# Binary_Blaster.net
KiCad netlist of a schematic drawn in EAGLE
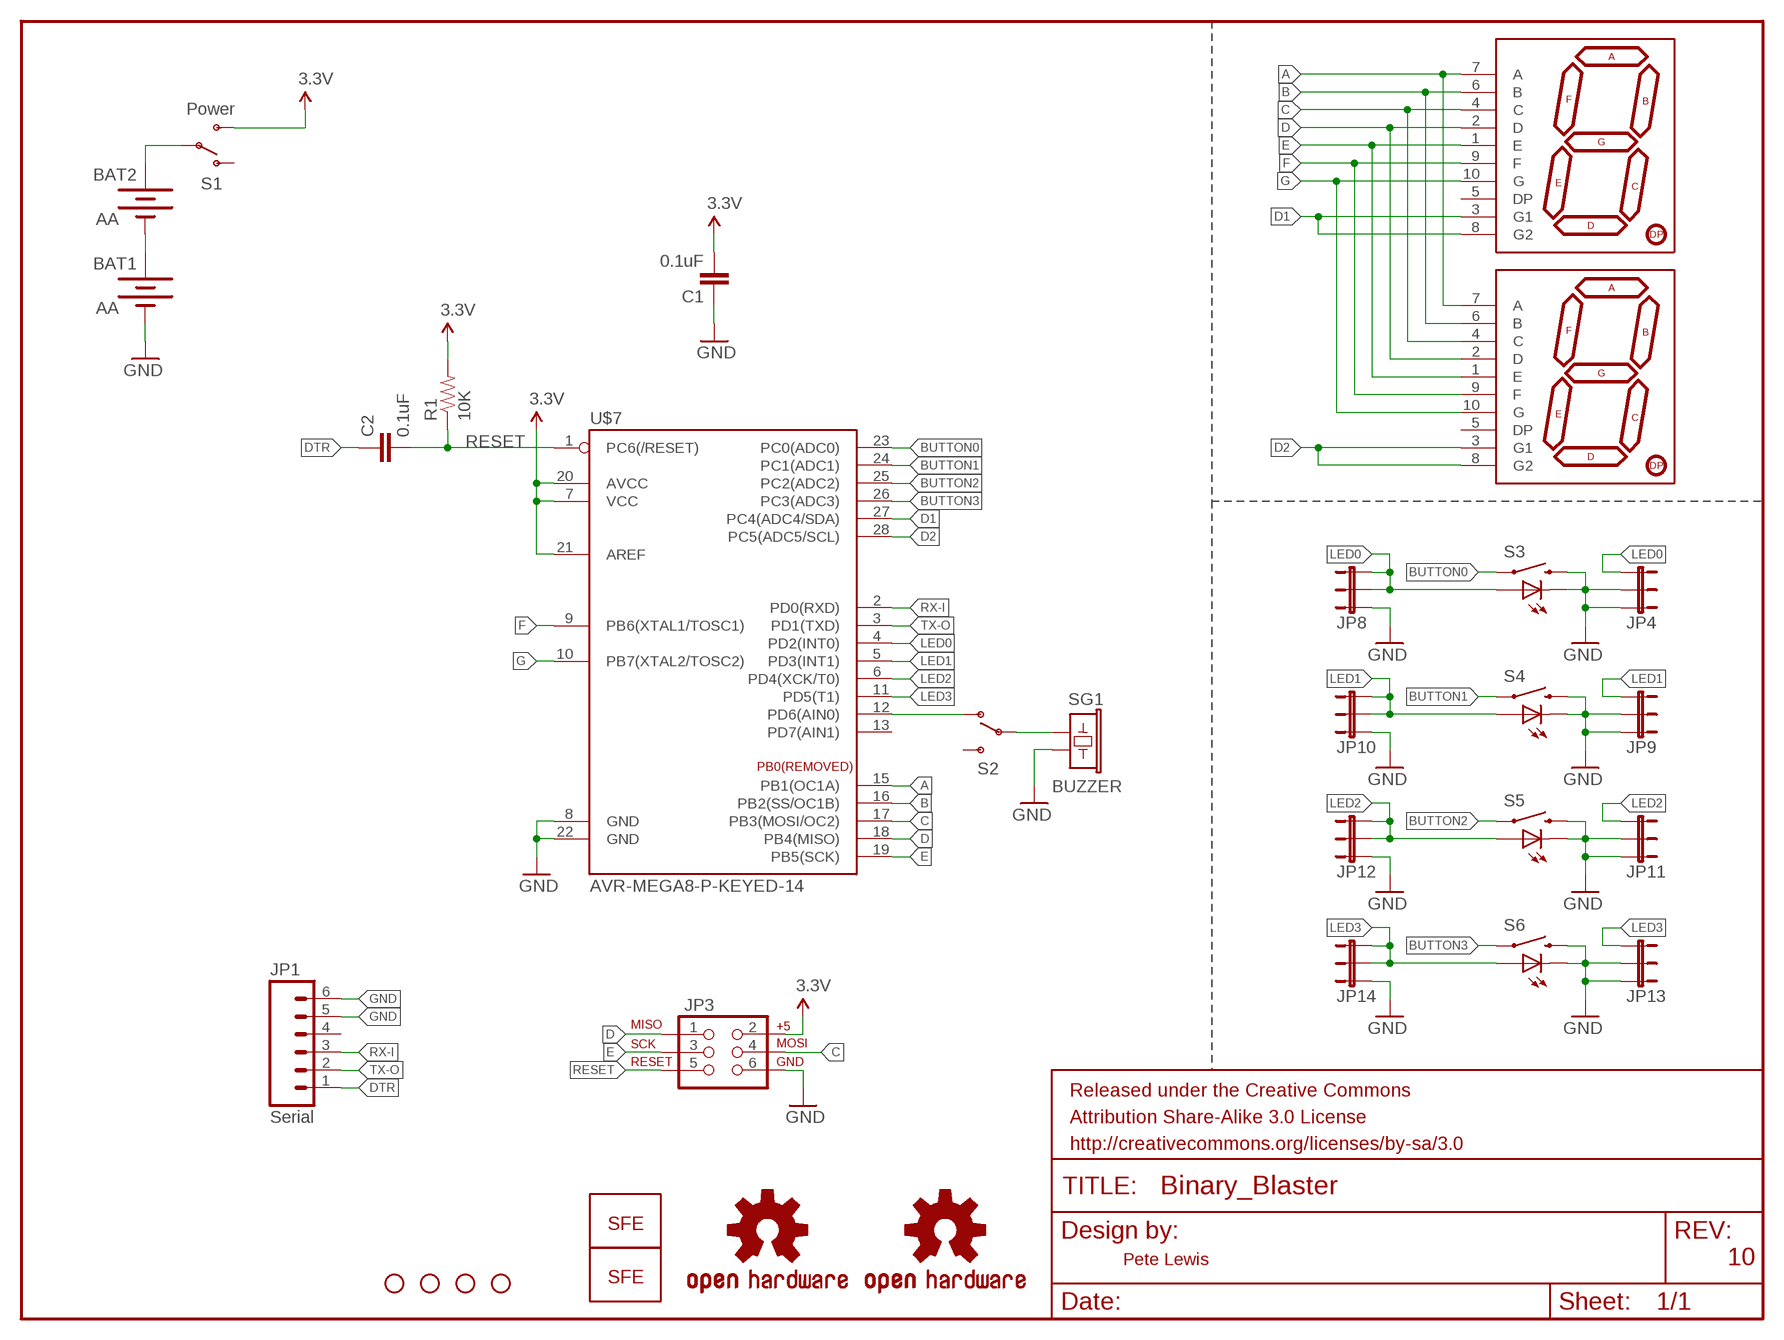
[diagram p0: schematic, sheet 1]

(export (version "E")
  (design (tool "Eeschema 10.0.6"))
  (components
    (comp (ref "BAT1")
      (value "AA")
      (footprint "eagle-import:BATTERY-AA-KIT")
      (libsource (lib "eagle-import") (part "BATTERYAA-KIT"))
    )
    (comp (ref "BAT2")
      (value "AA")
      (footprint "eagle-import:BATTERY-AA-KIT")
      (libsource (lib "eagle-import") (part "BATTERYAA-KIT"))
    )
    (comp (ref "C1")
      (value "0.1uF")
      (footprint "eagle-import:CAP-PTH-SMALL-KIT")
      (libsource (lib "eagle-import") (part "0.1UF-50V-20%(PTH)KIT-EZ"))
    )
    (comp (ref "C2")
      (value "0.1uF")
      (footprint "eagle-import:CAP-PTH-SMALL-KIT")
      (libsource (lib "eagle-import") (part "0.1UF-50V-20%(PTH)KIT-EZ"))
    )
    (comp (ref "FRAME1")
      (value "FRAME-LETTER")
      (footprint "eagle-import:CREATIVE_COMMONS")
      (libsource (lib "eagle-import") (part "FRAME-LETTER"))
    )
    (comp (ref "JP1")
      (value "Serial")
      (footprint "eagle-import:1X06-NOSILK")
      (libsource (lib "eagle-import") (part "M06-SFENOSILK"))
    )
    (comp (ref "JP2")
      (value "STAND-OFF")
      (footprint "eagle-import:STAND-OFF")
      (libsource (lib "eagle-import") (part "STAND-OFF"))
    )
    (comp (ref "JP3")
      (value "AVR_SPI_PRG_6NS")
      (footprint "eagle-import:2X3-NS")
      (libsource (lib "eagle-import") (part "AVR_SPI_PRG_6NS"))
    )
    (comp (ref "JP4")
      (value "JUMPER-3SMD")
      (footprint "eagle-import:SJ_3")
      (libsource (lib "eagle-import") (part "JUMPER-3SMD"))
    )
    (comp (ref "JP5")
      (value "STAND-OFF")
      (footprint "eagle-import:STAND-OFF")
      (libsource (lib "eagle-import") (part "STAND-OFF"))
    )
    (comp (ref "JP6")
      (value "STAND-OFF")
      (footprint "eagle-import:STAND-OFF")
      (libsource (lib "eagle-import") (part "STAND-OFF"))
    )
    (comp (ref "JP7")
      (value "STAND-OFF")
      (footprint "eagle-import:STAND-OFF")
      (libsource (lib "eagle-import") (part "STAND-OFF"))
    )
    (comp (ref "JP8")
      (value "JUMPER-3SMD")
      (footprint "eagle-import:SJ_3")
      (libsource (lib "eagle-import") (part "JUMPER-3SMD"))
    )
    (comp (ref "JP9")
      (value "JUMPER-3SMD")
      (footprint "eagle-import:SJ_3")
      (libsource (lib "eagle-import") (part "JUMPER-3SMD"))
    )
    (comp (ref "JP10")
      (value "JUMPER-3SMD")
      (footprint "eagle-import:SJ_3")
      (libsource (lib "eagle-import") (part "JUMPER-3SMD"))
    )
    (comp (ref "JP11")
      (value "JUMPER-3SMD")
      (footprint "eagle-import:SJ_3")
      (libsource (lib "eagle-import") (part "JUMPER-3SMD"))
    )
    (comp (ref "JP12")
      (value "JUMPER-3SMD")
      (footprint "eagle-import:SJ_3")
      (libsource (lib "eagle-import") (part "JUMPER-3SMD"))
    )
    (comp (ref "JP13")
      (value "JUMPER-3SMD")
      (footprint "eagle-import:SJ_3")
      (libsource (lib "eagle-import") (part "JUMPER-3SMD"))
    )
    (comp (ref "JP14")
      (value "JUMPER-3SMD")
      (footprint "eagle-import:SJ_3")
      (libsource (lib "eagle-import") (part "JUMPER-3SMD"))
    )
    (comp (ref "LOGO1")
      (value "LOGO-SFENEW")
      (footprint "eagle-import:SFE-NEW-WEBLOGO")
      (libsource (lib "eagle-import") (part "LOGO-SFENEW"))
    )
    (comp (ref "LOGO2")
      (value "LOGO-SFENEW")
      (footprint "eagle-import:SFE-NEW-WEBLOGO")
      (libsource (lib "eagle-import") (part "LOGO-SFENEW"))
    )
    (comp (ref "R1")
      (value "10K")
      (footprint "eagle-import:AXIAL-0.3-KIT")
      (libsource (lib "eagle-import") (part "10KOHM1/6W5%(PTH)KIT"))
    )
    (comp (ref "S1")
      (value "Power")
      (footprint "eagle-import:SWITCH-SPDT_KIT")
      (libsource (lib "eagle-import") (part "SWITCH-SPDTKIT"))
    )
    (comp (ref "S2")
      (value "SWITCH-SPDTKIT")
      (footprint "eagle-import:SWITCH-SPDT_KIT")
      (libsource (lib "eagle-import") (part "SWITCH-SPDTKIT"))
    )
    (comp (ref "S3")
      (value "SWITCH-MOMENTARY-LEDEZ")
      (footprint "eagle-import:TACTILE-PTH-LED-12MM-EZ")
      (libsource (lib "eagle-import") (part "SWITCH-MOMENTARY-LEDEZ"))
    )
    (comp (ref "S4")
      (value "SWITCH-MOMENTARY-LEDEZ")
      (footprint "eagle-import:TACTILE-PTH-LED-12MM-EZ")
      (libsource (lib "eagle-import") (part "SWITCH-MOMENTARY-LEDEZ"))
    )
    (comp (ref "S5")
      (value "SWITCH-MOMENTARY-LEDEZ")
      (footprint "eagle-import:TACTILE-PTH-LED-12MM-EZ")
      (libsource (lib "eagle-import") (part "SWITCH-MOMENTARY-LEDEZ"))
    )
    (comp (ref "S6")
      (value "SWITCH-MOMENTARY-LEDEZ")
      (footprint "eagle-import:TACTILE-PTH-LED-12MM-EZ")
      (libsource (lib "eagle-import") (part "SWITCH-MOMENTARY-LEDEZ"))
    )
    (comp (ref "SG1")
      (value "BUZZER")
      (footprint "eagle-import:BUZZER-12MM-KIT")
      (libsource (lib "eagle-import") (part "BUZZERPTH-KIT"))
    )
    (comp (ref "U$1")
      (value "7-SEGMENT-DISPLAY-1\"-REDEZ")
      (footprint "eagle-import:7-SEGMENT-1_PTH-EZ")
      (libsource (lib "eagle-import") (part "7-SEGMENT-DISPLAY-1{dblquote}-REDEZ"))
    )
    (comp (ref "U$2")
      (value "OSHW-LOGOL")
      (footprint "eagle-import:OSHW-LOGO-L")
      (libsource (lib "eagle-import") (part "OSHW-LOGOL"))
    )
    (comp (ref "U$3")
      (value "OSHW-LOGOS")
      (footprint "eagle-import:OSHW-LOGO-S")
      (libsource (lib "eagle-import") (part "OSHW-LOGOS"))
    )
    (comp (ref "U$6")
      (value "7-SEGMENT-DISPLAY-1\"-REDEZ")
      (footprint "eagle-import:7-SEGMENT-1_PTH-EZ")
      (libsource (lib "eagle-import") (part "7-SEGMENT-DISPLAY-1{dblquote}-REDEZ"))
    )
    (comp (ref "U$7")
      (value "AVR-MEGA8-P-KEYED-14")
      (footprint "eagle-import:DIL28-3_KEYED-14")
      (libsource (lib "eagle-import") (part "AVR-MEGA8-P-KEYED-14"))
    )
  )
  (nets
    (net (code "1") (name "3.3V") (class "Default")
      (node (ref "C1") (pin "2") (pinfunction "2_2") (pintype "passive"))
      (node (ref "JP3") (pin "2") (pinfunction "2_2") (pintype "passive"))
      (node (ref "R1") (pin "P$2") (pinfunction "2_P$2") (pintype "passive"))
      (node (ref "S1") (pin "3") (pinfunction "S_3") (pintype "passive"))
      (node (ref "U$7") (pin "20") (pinfunction "AVCC_20") (pintype "bidirectional"))
      (node (ref "U$7") (pin "21") (pinfunction "AREF_21") (pintype "bidirectional"))
      (node (ref "U$7") (pin "7") (pinfunction "VCC_7") (pintype "bidirectional"))
    )
    (net (code "2") (name "A") (class "Default")
      (node (ref "U$1") (pin "7") (pinfunction "A_7") (pintype "bidirectional"))
      (node (ref "U$6") (pin "7") (pinfunction "A_7") (pintype "bidirectional"))
      (node (ref "U$7") (pin "15") (pinfunction "PB1(OC1A)_15") (pintype "bidirectional"))
    )
    (net (code "3") (name "B") (class "Default")
      (node (ref "U$1") (pin "6") (pinfunction "B_6") (pintype "bidirectional"))
      (node (ref "U$6") (pin "6") (pinfunction "B_6") (pintype "bidirectional"))
      (node (ref "U$7") (pin "16") (pinfunction "PB2(SS/OC1B)_16") (pintype "bidirectional"))
    )
    (net (code "4") (name "BUTTON0") (class "Default")
      (node (ref "S3") (pin "4") (pinfunction "1_4") (pintype "passive"))
      (node (ref "U$7") (pin "23") (pinfunction "PC0(ADC0)_23") (pintype "bidirectional"))
    )
    (net (code "5") (name "BUTTON1") (class "Default")
      (node (ref "S4") (pin "4") (pinfunction "1_4") (pintype "passive"))
      (node (ref "U$7") (pin "24") (pinfunction "PC1(ADC1)_24") (pintype "bidirectional"))
    )
    (net (code "6") (name "BUTTON2") (class "Default")
      (node (ref "S5") (pin "4") (pinfunction "1_4") (pintype "passive"))
      (node (ref "U$7") (pin "25") (pinfunction "PC2(ADC2)_25") (pintype "bidirectional"))
    )
    (net (code "7") (name "BUTTON3") (class "Default")
      (node (ref "S6") (pin "4") (pinfunction "1_4") (pintype "passive"))
      (node (ref "U$7") (pin "26") (pinfunction "PC3(ADC3)_26") (pintype "bidirectional"))
    )
    (net (code "8") (name "C") (class "Default")
      (node (ref "JP3") (pin "4") (pinfunction "4_4") (pintype "passive"))
      (node (ref "U$1") (pin "4") (pinfunction "C_4") (pintype "bidirectional"))
      (node (ref "U$6") (pin "4") (pinfunction "C_4") (pintype "bidirectional"))
      (node (ref "U$7") (pin "17") (pinfunction "PB3(MOSI/OC2)_17") (pintype "bidirectional"))
    )
    (net (code "9") (name "D") (class "Default")
      (node (ref "JP3") (pin "1") (pinfunction "1_1") (pintype "passive"))
      (node (ref "U$1") (pin "2") (pinfunction "D_2") (pintype "bidirectional"))
      (node (ref "U$6") (pin "2") (pinfunction "D_2") (pintype "bidirectional"))
      (node (ref "U$7") (pin "18") (pinfunction "PB4(MISO)_18") (pintype "bidirectional"))
    )
    (net (code "10") (name "D1") (class "Default")
      (node (ref "U$1") (pin "3") (pinfunction "G1_3") (pintype "bidirectional"))
      (node (ref "U$1") (pin "8") (pinfunction "G2_8") (pintype "bidirectional"))
      (node (ref "U$7") (pin "27") (pinfunction "PC4(ADC4/SDA)_27") (pintype "bidirectional"))
    )
    (net (code "11") (name "D2") (class "Default")
      (node (ref "U$6") (pin "3") (pinfunction "G1_3") (pintype "bidirectional"))
      (node (ref "U$6") (pin "8") (pinfunction "G2_8") (pintype "bidirectional"))
      (node (ref "U$7") (pin "28") (pinfunction "PC5(ADC5/SCL)_28") (pintype "bidirectional"))
    )
    (net (code "12") (name "DTR") (class "Default")
      (node (ref "C2") (pin "1") (pinfunction "1_1") (pintype "passive"))
      (node (ref "JP1") (pin "1") (pinfunction "1_1") (pintype "passive"))
    )
    (net (code "13") (name "E") (class "Default")
      (node (ref "JP3") (pin "3") (pinfunction "3_3") (pintype "passive"))
      (node (ref "U$1") (pin "1") (pinfunction "E_1") (pintype "bidirectional"))
      (node (ref "U$6") (pin "1") (pinfunction "E_1") (pintype "bidirectional"))
      (node (ref "U$7") (pin "19") (pinfunction "PB5(SCK)_19") (pintype "bidirectional"))
    )
    (net (code "14") (name "F") (class "Default")
      (node (ref "U$1") (pin "9") (pinfunction "F_9") (pintype "bidirectional"))
      (node (ref "U$6") (pin "9") (pinfunction "F_9") (pintype "bidirectional"))
      (node (ref "U$7") (pin "9") (pinfunction "PB6(XTAL1/TOSC1)_9") (pintype "bidirectional"))
    )
    (net (code "15") (name "G") (class "Default")
      (node (ref "U$1") (pin "10") (pinfunction "G_10") (pintype "bidirectional"))
      (node (ref "U$6") (pin "10") (pinfunction "G_10") (pintype "bidirectional"))
      (node (ref "U$7") (pin "10") (pinfunction "PB7(XTAL2/TOSC2)_10") (pintype "bidirectional"))
    )
    (net (code "16") (name "GND") (class "Default")
      (node (ref "BAT1") (pin "GND@1") (pinfunction "-_GND@1") (pintype "power_in"))
      (node (ref "C1") (pin "1") (pinfunction "1_1") (pintype "passive"))
      (node (ref "JP1") (pin "5") (pinfunction "5_5") (pintype "passive"))
      (node (ref "JP1") (pin "6") (pinfunction "6_6") (pintype "passive"))
      (node (ref "JP10") (pin "1") (pinfunction "1_1") (pintype "passive"))
      (node (ref "JP11") (pin "2") (pinfunction "2_2") (pintype "passive"))
      (node (ref "JP11") (pin "3") (pinfunction "3_3") (pintype "passive"))
      (node (ref "JP12") (pin "1") (pinfunction "1_1") (pintype "passive"))
      (node (ref "JP13") (pin "2") (pinfunction "2_2") (pintype "passive"))
      (node (ref "JP13") (pin "3") (pinfunction "3_3") (pintype "passive"))
      (node (ref "JP14") (pin "1") (pinfunction "1_1") (pintype "passive"))
      (node (ref "JP3") (pin "6") (pinfunction "6_6") (pintype "passive"))
      (node (ref "JP4") (pin "2") (pinfunction "2_2") (pintype "passive"))
      (node (ref "JP4") (pin "3") (pinfunction "3_3") (pintype "passive"))
      (node (ref "JP8") (pin "1") (pinfunction "1_1") (pintype "passive"))
      (node (ref "JP9") (pin "2") (pinfunction "2_2") (pintype "passive"))
      (node (ref "JP9") (pin "3") (pinfunction "3_3") (pintype "passive"))
      (node (ref "S3") (pin "2") (pinfunction "2_2") (pintype "passive"))
      (node (ref "S3") (pin "C") (pinfunction "C_C") (pintype "passive"))
      (node (ref "S4") (pin "2") (pinfunction "2_2") (pintype "passive"))
      (node (ref "S4") (pin "C") (pinfunction "C_C") (pintype "passive"))
      (node (ref "S5") (pin "2") (pinfunction "2_2") (pintype "passive"))
      (node (ref "S5") (pin "C") (pinfunction "C_C") (pintype "passive"))
      (node (ref "S6") (pin "2") (pinfunction "2_2") (pintype "passive"))
      (node (ref "S6") (pin "C") (pinfunction "C_C") (pintype "passive"))
      (node (ref "SG1") (pin "-") (pinfunction "2_-") (pintype "passive"))
      (node (ref "U$7") (pin "22") (pinfunction "GND_22") (pintype "bidirectional"))
      (node (ref "U$7") (pin "8") (pinfunction "GND_8") (pintype "bidirectional"))
    )
    (net (code "17") (name "LED0") (class "Default")
      (node (ref "JP4") (pin "1") (pinfunction "1_1") (pintype "passive"))
      (node (ref "JP8") (pin "2") (pinfunction "2_2") (pintype "passive"))
      (node (ref "JP8") (pin "3") (pinfunction "3_3") (pintype "passive"))
      (node (ref "S3") (pin "A") (pinfunction "A_A") (pintype "passive"))
      (node (ref "U$7") (pin "4") (pinfunction "PD2(INT0)_4") (pintype "bidirectional"))
    )
    (net (code "18") (name "LED1") (class "Default")
      (node (ref "JP10") (pin "2") (pinfunction "2_2") (pintype "passive"))
      (node (ref "JP10") (pin "3") (pinfunction "3_3") (pintype "passive"))
      (node (ref "JP9") (pin "1") (pinfunction "1_1") (pintype "passive"))
      (node (ref "S4") (pin "A") (pinfunction "A_A") (pintype "passive"))
      (node (ref "U$7") (pin "5") (pinfunction "PD3(INT1)_5") (pintype "bidirectional"))
    )
    (net (code "19") (name "LED2") (class "Default")
      (node (ref "JP11") (pin "1") (pinfunction "1_1") (pintype "passive"))
      (node (ref "JP12") (pin "2") (pinfunction "2_2") (pintype "passive"))
      (node (ref "JP12") (pin "3") (pinfunction "3_3") (pintype "passive"))
      (node (ref "S5") (pin "A") (pinfunction "A_A") (pintype "passive"))
      (node (ref "U$7") (pin "6") (pinfunction "PD4(XCK/T0)_6") (pintype "bidirectional"))
    )
    (net (code "20") (name "LED3") (class "Default")
      (node (ref "JP13") (pin "1") (pinfunction "1_1") (pintype "passive"))
      (node (ref "JP14") (pin "2") (pinfunction "2_2") (pintype "passive"))
      (node (ref "JP14") (pin "3") (pinfunction "3_3") (pintype "passive"))
      (node (ref "S6") (pin "A") (pinfunction "A_A") (pintype "passive"))
      (node (ref "U$7") (pin "11") (pinfunction "PD5(T1)_11") (pintype "bidirectional"))
    )
    (net (code "21") (name "Net-(BAT1-+)") (class "Default")
      (node (ref "BAT1") (pin "PWR@1") (pinfunction "+_PWR@1") (pintype "power_in"))
      (node (ref "BAT2") (pin "GND@1") (pinfunction "-_GND@1") (pintype "power_in"))
    )
    (net (code "22") (name "Net-(BAT2-+)") (class "Default")
      (node (ref "BAT2") (pin "PWR@1") (pinfunction "+_PWR@1") (pintype "power_in"))
      (node (ref "S1") (pin "2") (pinfunction "P_2") (pintype "passive"))
    )
    (net (code "23") (name "Net-(S2-O)") (class "Default")
      (node (ref "S2") (pin "1") (pinfunction "O_1") (pintype "passive"))
      (node (ref "U$7") (pin "12") (pinfunction "PD6(AIN0)_12") (pintype "bidirectional"))
    )
    (net (code "24") (name "Net-(S2-P)") (class "Default")
      (node (ref "S2") (pin "2") (pinfunction "P_2") (pintype "passive"))
      (node (ref "SG1") (pin "+") (pinfunction "1_+") (pintype "passive"))
    )
    (net (code "25") (name "RESET") (class "Default")
      (node (ref "C2") (pin "2") (pinfunction "2_2") (pintype "passive"))
      (node (ref "JP3") (pin "5") (pinfunction "5_5") (pintype "passive"))
      (node (ref "R1") (pin "P$1") (pinfunction "1_P$1") (pintype "passive"))
      (node (ref "U$7") (pin "1") (pinfunction "PC6(/RESET)_1") (pintype "bidirectional"))
    )
    (net (code "26") (name "RX-I") (class "Default")
      (node (ref "JP1") (pin "3") (pinfunction "3_3") (pintype "passive"))
      (node (ref "U$7") (pin "2") (pinfunction "PD0(RXD)_2") (pintype "bidirectional"))
    )
    (net (code "27") (name "TX-O") (class "Default")
      (node (ref "JP1") (pin "2") (pinfunction "2_2") (pintype "passive"))
      (node (ref "U$7") (pin "3") (pinfunction "PD1(TXD)_3") (pintype "bidirectional"))
    )
    (net (code "28") (name "unconnected-(JP1-Pad4)") (class "Default")
      (node (ref "JP1") (pin "4") (pinfunction "4_4") (pintype "passive"))
    )
    (net (code "29") (name "unconnected-(S1-O-Pad1)") (class "Default")
      (node (ref "S1") (pin "1") (pinfunction "O_1") (pintype "passive"))
    )
    (net (code "30") (name "unconnected-(S2-S-Pad3)") (class "Default")
      (node (ref "S2") (pin "3") (pinfunction "S_3") (pintype "passive"))
    )
    (net (code "31") (name "unconnected-(U$1-DP-Pad5)") (class "Default")
      (node (ref "U$1") (pin "5") (pinfunction "DP_5") (pintype "bidirectional"))
    )
    (net (code "32") (name "unconnected-(U$6-DP-Pad5)") (class "Default")
      (node (ref "U$6") (pin "5") (pinfunction "DP_5") (pintype "bidirectional"))
    )
    (net (code "33") (name "unconnected-(U$7-PD7(AIN1)-Pad13)") (class "Default")
      (node (ref "U$7") (pin "13") (pinfunction "PD7(AIN1)_13") (pintype "bidirectional"))
    )
  )
)
